# vewa-filters.net
KiCad netlist of a schematic drawn in EAGLE
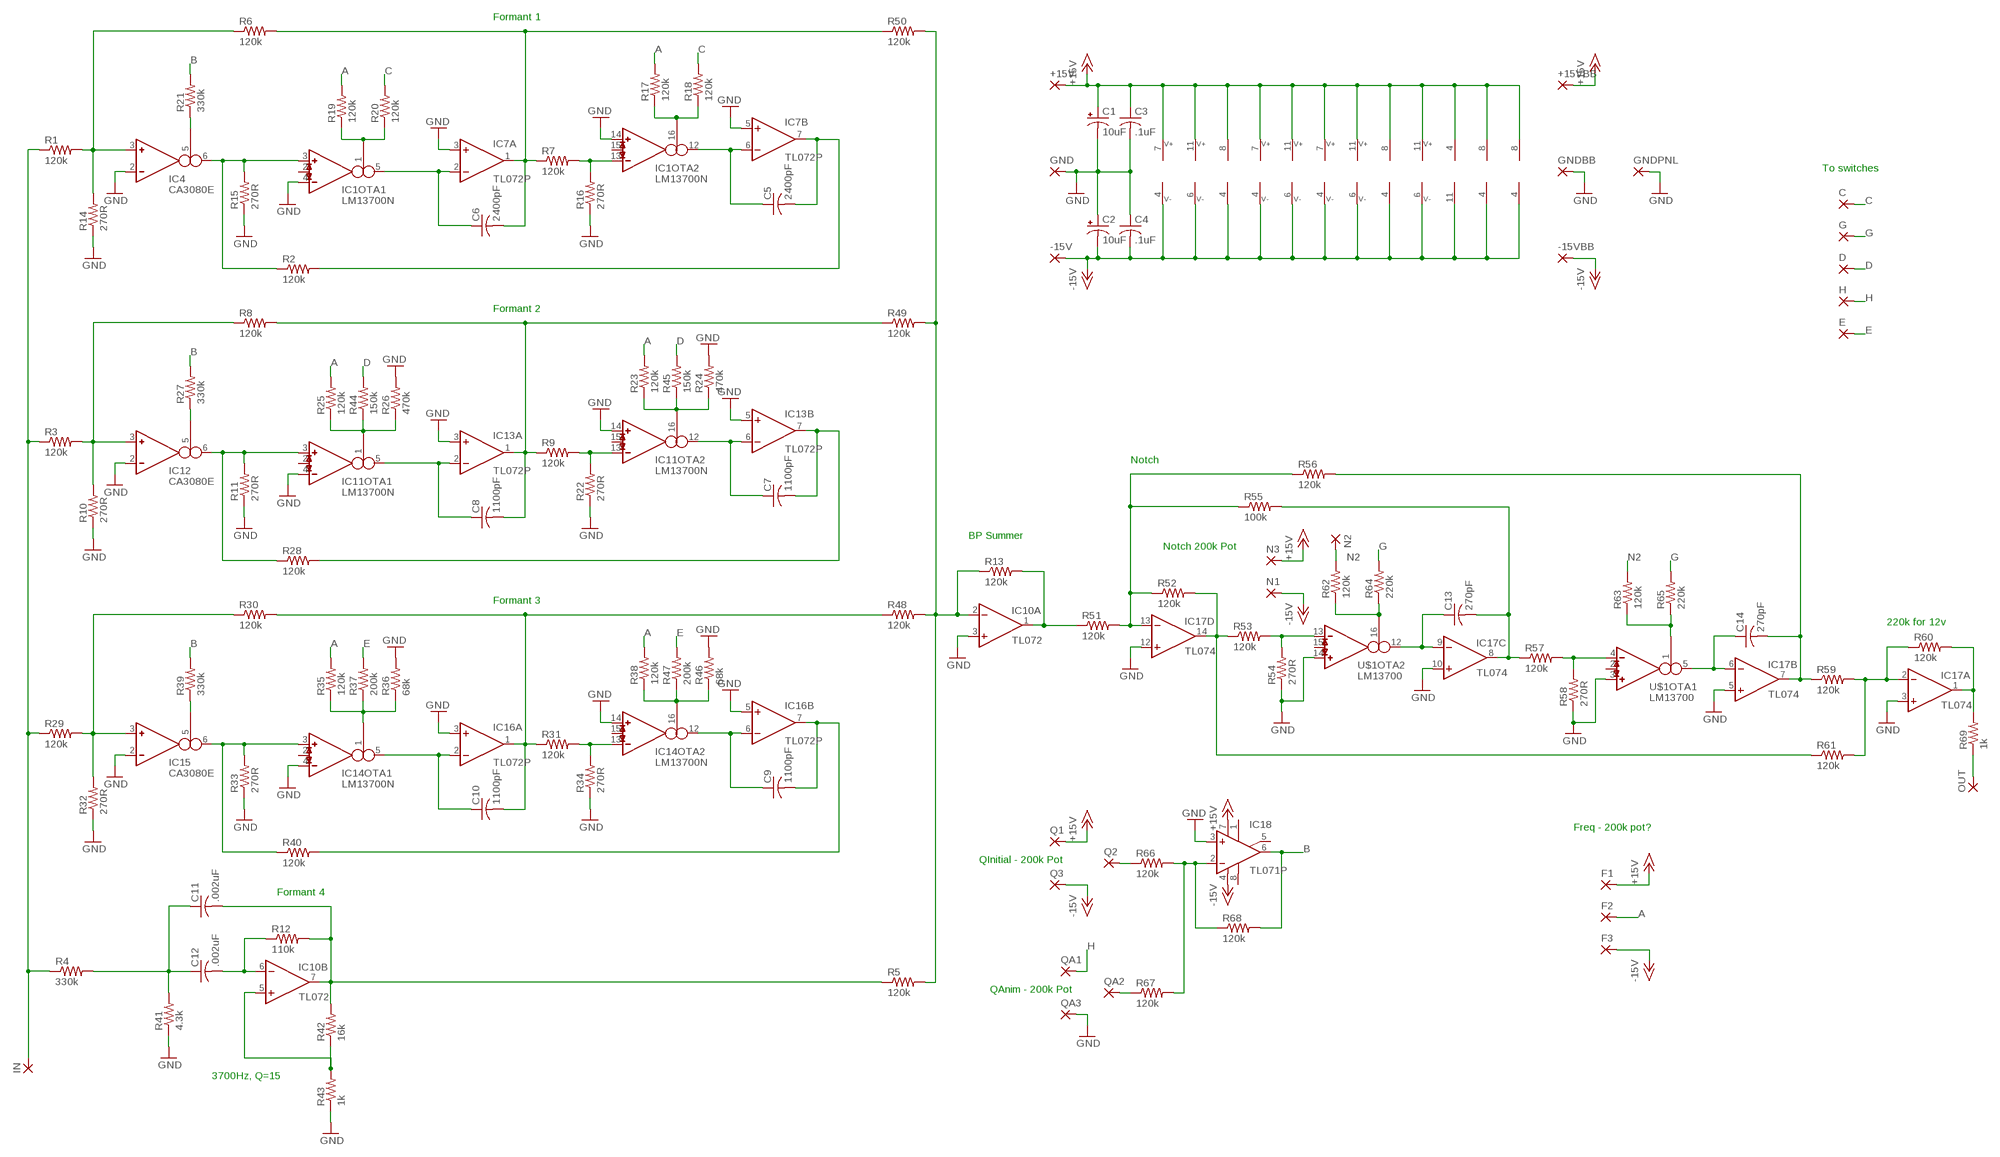
[diagram p0: schematic, sheet 1]

(export (version "E")
  (design (tool "Eeschema 10.0.6"))
  (components
    (comp (ref "+15V")
      (value "2,54/1,0")
      (footprint "eagle-import:2,54_1,0")
      (libsource (lib "eagle-import") (part "2,54/1,0"))
    )
    (comp (ref "+15VBB")
      (value "2,54/1,0")
      (footprint "eagle-import:2,54_1,0")
      (libsource (lib "eagle-import") (part "2,54/1,0"))
    )
    (comp (ref "-15V")
      (value "2,54/1,0")
      (footprint "eagle-import:2,54_1,0")
      (libsource (lib "eagle-import") (part "2,54/1,0"))
    )
    (comp (ref "-15VBB")
      (value "2,54/1,0")
      (footprint "eagle-import:2,54_1,0")
      (libsource (lib "eagle-import") (part "2,54/1,0"))
    )
    (comp (ref "C")
      (value "2,54/1,0")
      (footprint "eagle-import:2,54_1,0")
      (libsource (lib "eagle-import") (part "2,54/1,0"))
    )
    (comp (ref "C1")
      (value "10uF")
      (footprint "eagle-import:E2,5-5")
      (libsource (lib "eagle-import") (part "CPOL-USE2.5-5"))
    )
    (comp (ref "C2")
      (value "10uF")
      (footprint "eagle-import:E2,5-5")
      (libsource (lib "eagle-import") (part "CPOL-USE2.5-5"))
    )
    (comp (ref "C3")
      (value ".1uF")
      (footprint "eagle-import:C050-025X075")
      (libsource (lib "eagle-import") (part "C-US050-025X075"))
    )
    (comp (ref "C4")
      (value ".1uF")
      (footprint "eagle-import:C050-025X075")
      (libsource (lib "eagle-import") (part "C-US050-025X075"))
    )
    (comp (ref "C5")
      (value "2400pF")
      (footprint "eagle-import:C050-025X075")
      (libsource (lib "eagle-import") (part "C-US050-025X075"))
    )
    (comp (ref "C6")
      (value "2400pF")
      (footprint "eagle-import:C050-025X075")
      (libsource (lib "eagle-import") (part "C-US050-025X075"))
    )
    (comp (ref "C7")
      (value "1100pF")
      (footprint "eagle-import:C050-025X075")
      (libsource (lib "eagle-import") (part "C-US050-025X075"))
    )
    (comp (ref "C8")
      (value "1100pF")
      (footprint "eagle-import:C050-025X075")
      (libsource (lib "eagle-import") (part "C-US050-025X075"))
    )
    (comp (ref "C9")
      (value "1100pF")
      (footprint "eagle-import:C050-025X075")
      (libsource (lib "eagle-import") (part "C-US050-025X075"))
    )
    (comp (ref "C10")
      (value "1100pF")
      (footprint "eagle-import:C050-025X075")
      (libsource (lib "eagle-import") (part "C-US050-025X075"))
    )
    (comp (ref "C11")
      (value ".002uF")
      (footprint "eagle-import:C050-025X075")
      (libsource (lib "eagle-import") (part "C-US050-025X075"))
    )
    (comp (ref "C12")
      (value ".002uF")
      (footprint "eagle-import:C050-025X075")
      (libsource (lib "eagle-import") (part "C-US050-025X075"))
    )
    (comp (ref "C13")
      (value "270pF")
      (footprint "eagle-import:C050-025X075")
      (libsource (lib "eagle-import") (part "C-US050-025X075"))
    )
    (comp (ref "C14")
      (value "270pF")
      (footprint "eagle-import:C050-025X075")
      (libsource (lib "eagle-import") (part "C-US050-025X075"))
    )
    (comp (ref "D")
      (value "2,54/1,0")
      (footprint "eagle-import:2,54_1,0")
      (libsource (lib "eagle-import") (part "2,54/1,0"))
    )
    (comp (ref "E")
      (value "2,54/1,0")
      (footprint "eagle-import:2,54_1,0")
      (libsource (lib "eagle-import") (part "2,54/1,0"))
    )
    (comp (ref "F1")
      (value "2,54/1,0")
      (footprint "eagle-import:2,54_1,0")
      (libsource (lib "eagle-import") (part "2,54/1,0"))
    )
    (comp (ref "F2")
      (value "2,54/1,0")
      (footprint "eagle-import:2,54_1,0")
      (libsource (lib "eagle-import") (part "2,54/1,0"))
    )
    (comp (ref "F3")
      (value "2,54/1,0")
      (footprint "eagle-import:2,54_1,0")
      (libsource (lib "eagle-import") (part "2,54/1,0"))
    )
    (comp (ref "G")
      (value "2,54/1,0")
      (footprint "eagle-import:2,54_1,0")
      (libsource (lib "eagle-import") (part "2,54/1,0"))
    )
    (comp (ref "GND")
      (value "2,54/1,0")
      (footprint "eagle-import:2,54_1,0")
      (libsource (lib "eagle-import") (part "2,54/1,0"))
    )
    (comp (ref "GNDBB")
      (value "2,54/1,0")
      (footprint "eagle-import:2,54_1,0")
      (libsource (lib "eagle-import") (part "2,54/1,0"))
    )
    (comp (ref "GNDPNL")
      (value "2,54/1,0")
      (footprint "eagle-import:2,54_1,0")
      (libsource (lib "eagle-import") (part "2,54/1,0"))
    )
    (comp (ref "H")
      (value "2,54/1,0")
      (footprint "eagle-import:2,54_1,0")
      (libsource (lib "eagle-import") (part "2,54/1,0"))
    )
    (comp (ref "IC1")
      (value "LM13700N")
      (footprint "eagle-import:DIL16")
      (libsource (lib "eagle-import") (part "LM13700N"))
    )
    (comp (ref "IC4")
      (value "CA3080E")
      (footprint "eagle-import:DIL08")
      (libsource (lib "eagle-import") (part "CA3080E"))
    )
    (comp (ref "IC7")
      (value "TL072P")
      (footprint "eagle-import:DIL08")
      (libsource (lib "eagle-import") (part "TL072P"))
    )
    (comp (ref "IC10")
      (value "TL072")
      (footprint "eagle-import:DIL08")
      (libsource (lib "eagle-import") (part "TL072-TOPP"))
    )
    (comp (ref "IC11")
      (value "LM13700N")
      (footprint "eagle-import:DIL16")
      (libsource (lib "eagle-import") (part "LM13700N"))
    )
    (comp (ref "IC12")
      (value "CA3080E")
      (footprint "eagle-import:DIL08")
      (libsource (lib "eagle-import") (part "CA3080E"))
    )
    (comp (ref "IC13")
      (value "TL072P")
      (footprint "eagle-import:DIL08")
      (libsource (lib "eagle-import") (part "TL072P"))
    )
    (comp (ref "IC14")
      (value "LM13700N")
      (footprint "eagle-import:DIL16")
      (libsource (lib "eagle-import") (part "LM13700N"))
    )
    (comp (ref "IC15")
      (value "CA3080E")
      (footprint "eagle-import:DIL08")
      (libsource (lib "eagle-import") (part "CA3080E"))
    )
    (comp (ref "IC16")
      (value "TL072P")
      (footprint "eagle-import:DIL08")
      (libsource (lib "eagle-import") (part "TL072P"))
    )
    (comp (ref "IC17")
      (value "TL074")
      (footprint "eagle-import:DIL14")
      (libsource (lib "eagle-import") (part "TL074-TOPP"))
    )
    (comp (ref "IC18")
      (value "TL071P")
      (footprint "eagle-import:DIL08")
      (libsource (lib "eagle-import") (part "TL071P"))
    )
    (comp (ref "IN")
      (value "2,54/1,0")
      (footprint "eagle-import:2,54_1,0")
      (libsource (lib "eagle-import") (part "2,54/1,0"))
    )
    (comp (ref "N1")
      (value "2,54/1,0")
      (footprint "eagle-import:2,54_1,0")
      (libsource (lib "eagle-import") (part "2,54/1,0"))
    )
    (comp (ref "N2")
      (value "2,54/1,0")
      (footprint "eagle-import:2,54_1,0")
      (libsource (lib "eagle-import") (part "2,54/1,0"))
    )
    (comp (ref "N3")
      (value "2,54/1,0")
      (footprint "eagle-import:2,54_1,0")
      (libsource (lib "eagle-import") (part "2,54/1,0"))
    )
    (comp (ref "OUT")
      (value "2,54/1,0")
      (footprint "eagle-import:2,54_1,0")
      (libsource (lib "eagle-import") (part "2,54/1,0"))
    )
    (comp (ref "Q1")
      (value "2,54/1,0")
      (footprint "eagle-import:2,54_1,0")
      (libsource (lib "eagle-import") (part "2,54/1,0"))
    )
    (comp (ref "Q2")
      (value "2,54/1,0")
      (footprint "eagle-import:2,54_1,0")
      (libsource (lib "eagle-import") (part "2,54/1,0"))
    )
    (comp (ref "Q3")
      (value "2,54/1,0")
      (footprint "eagle-import:2,54_1,0")
      (libsource (lib "eagle-import") (part "2,54/1,0"))
    )
    (comp (ref "QA1")
      (value "2,54/1,0")
      (footprint "eagle-import:2,54_1,0")
      (libsource (lib "eagle-import") (part "2,54/1,0"))
    )
    (comp (ref "QA2")
      (value "2,54/1,0")
      (footprint "eagle-import:2,54_1,0")
      (libsource (lib "eagle-import") (part "2,54/1,0"))
    )
    (comp (ref "QA3")
      (value "2,54/1,0")
      (footprint "eagle-import:2,54_1,0")
      (libsource (lib "eagle-import") (part "2,54/1,0"))
    )
    (comp (ref "R1")
      (value "120k")
      (footprint "eagle-import:0207_10")
      (libsource (lib "eagle-import") (part "R-US_0207/10"))
    )
    (comp (ref "R2")
      (value "120k")
      (footprint "eagle-import:0207_10")
      (libsource (lib "eagle-import") (part "R-US_0207/10"))
    )
    (comp (ref "R3")
      (value "120k")
      (footprint "eagle-import:0207_10")
      (libsource (lib "eagle-import") (part "R-US_0207/10"))
    )
    (comp (ref "R4")
      (value "330k")
      (footprint "eagle-import:0207_10")
      (libsource (lib "eagle-import") (part "R-US_0207/10"))
    )
    (comp (ref "R5")
      (value "120k")
      (footprint "eagle-import:0207_10")
      (libsource (lib "eagle-import") (part "R-US_0207/10"))
    )
    (comp (ref "R6")
      (value "120k")
      (footprint "eagle-import:0207_10")
      (libsource (lib "eagle-import") (part "R-US_0207/10"))
    )
    (comp (ref "R7")
      (value "120k")
      (footprint "eagle-import:0207_10")
      (libsource (lib "eagle-import") (part "R-US_0207/10"))
    )
    (comp (ref "R8")
      (value "120k")
      (footprint "eagle-import:0207_10")
      (libsource (lib "eagle-import") (part "R-US_0207/10"))
    )
    (comp (ref "R9")
      (value "120k")
      (footprint "eagle-import:0207_10")
      (libsource (lib "eagle-import") (part "R-US_0207/10"))
    )
    (comp (ref "R10")
      (value "270R")
      (footprint "eagle-import:0207_10")
      (libsource (lib "eagle-import") (part "R-US_0207/10"))
    )
    (comp (ref "R11")
      (value "270R")
      (footprint "eagle-import:0207_10")
      (libsource (lib "eagle-import") (part "R-US_0207/10"))
    )
    (comp (ref "R12")
      (value "110k")
      (footprint "eagle-import:0207_10")
      (libsource (lib "eagle-import") (part "R-US_0207/10"))
    )
    (comp (ref "R13")
      (value "120k")
      (footprint "eagle-import:0207_10")
      (libsource (lib "eagle-import") (part "R-US_0207/10"))
    )
    (comp (ref "R14")
      (value "270R")
      (footprint "eagle-import:0207_10")
      (libsource (lib "eagle-import") (part "R-US_0207/10"))
    )
    (comp (ref "R15")
      (value "270R")
      (footprint "eagle-import:0207_10")
      (libsource (lib "eagle-import") (part "R-US_0207/10"))
    )
    (comp (ref "R16")
      (value "270R")
      (footprint "eagle-import:0207_10")
      (libsource (lib "eagle-import") (part "R-US_0207/10"))
    )
    (comp (ref "R17")
      (value "120k")
      (footprint "eagle-import:0207_10")
      (libsource (lib "eagle-import") (part "R-US_0207/10"))
    )
    (comp (ref "R18")
      (value "120k")
      (footprint "eagle-import:0207_10")
      (libsource (lib "eagle-import") (part "R-US_0207/10"))
    )
    (comp (ref "R19")
      (value "120k")
      (footprint "eagle-import:0207_10")
      (libsource (lib "eagle-import") (part "R-US_0207/10"))
    )
    (comp (ref "R20")
      (value "120k")
      (footprint "eagle-import:0207_10")
      (libsource (lib "eagle-import") (part "R-US_0207/10"))
    )
    (comp (ref "R21")
      (value "330k")
      (footprint "eagle-import:0207_10")
      (libsource (lib "eagle-import") (part "R-US_0207/10"))
    )
    (comp (ref "R22")
      (value "270R")
      (footprint "eagle-import:0207_10")
      (libsource (lib "eagle-import") (part "R-US_0207/10"))
    )
    (comp (ref "R23")
      (value "120k")
      (footprint "eagle-import:0207_10")
      (libsource (lib "eagle-import") (part "R-US_0207/10"))
    )
    (comp (ref "R24")
      (value "470k")
      (footprint "eagle-import:0207_10")
      (libsource (lib "eagle-import") (part "R-US_0207/10"))
    )
    (comp (ref "R25")
      (value "120k")
      (footprint "eagle-import:0207_10")
      (libsource (lib "eagle-import") (part "R-US_0207/10"))
    )
    (comp (ref "R26")
      (value "470k")
      (footprint "eagle-import:0207_10")
      (libsource (lib "eagle-import") (part "R-US_0207/10"))
    )
    (comp (ref "R27")
      (value "330k")
      (footprint "eagle-import:0207_10")
      (libsource (lib "eagle-import") (part "R-US_0207/10"))
    )
    (comp (ref "R28")
      (value "120k")
      (footprint "eagle-import:0207_10")
      (libsource (lib "eagle-import") (part "R-US_0207/10"))
    )
    (comp (ref "R29")
      (value "120k")
      (footprint "eagle-import:0207_10")
      (libsource (lib "eagle-import") (part "R-US_0207/10"))
    )
    (comp (ref "R30")
      (value "120k")
      (footprint "eagle-import:0207_10")
      (libsource (lib "eagle-import") (part "R-US_0207/10"))
    )
    (comp (ref "R31")
      (value "120k")
      (footprint "eagle-import:0207_10")
      (libsource (lib "eagle-import") (part "R-US_0207/10"))
    )
    (comp (ref "R32")
      (value "270R")
      (footprint "eagle-import:0207_10")
      (libsource (lib "eagle-import") (part "R-US_0207/10"))
    )
    (comp (ref "R33")
      (value "270R")
      (footprint "eagle-import:0207_10")
      (libsource (lib "eagle-import") (part "R-US_0207/10"))
    )
    (comp (ref "R34")
      (value "270R")
      (footprint "eagle-import:0207_10")
      (libsource (lib "eagle-import") (part "R-US_0207/10"))
    )
    (comp (ref "R35")
      (value "120k")
      (footprint "eagle-import:0207_10")
      (libsource (lib "eagle-import") (part "R-US_0207/10"))
    )
    (comp (ref "R36")
      (value "68k")
      (footprint "eagle-import:0207_10")
      (libsource (lib "eagle-import") (part "R-US_0207/10"))
    )
    (comp (ref "R37")
      (value "200k")
      (footprint "eagle-import:0207_10")
      (libsource (lib "eagle-import") (part "R-US_0207/10"))
    )
    (comp (ref "R38")
      (value "120k")
      (footprint "eagle-import:0207_10")
      (libsource (lib "eagle-import") (part "R-US_0207/10"))
    )
    (comp (ref "R39")
      (value "330k")
      (footprint "eagle-import:0207_10")
      (libsource (lib "eagle-import") (part "R-US_0207/10"))
    )
    (comp (ref "R40")
      (value "120k")
      (footprint "eagle-import:0207_10")
      (libsource (lib "eagle-import") (part "R-US_0207/10"))
    )
    (comp (ref "R41")
      (value "4.3k")
      (footprint "eagle-import:0207_10")
      (libsource (lib "eagle-import") (part "R-US_0207/10"))
    )
    (comp (ref "R42")
      (value "16k")
      (footprint "eagle-import:0207_10")
      (libsource (lib "eagle-import") (part "R-US_0207/10"))
    )
    (comp (ref "R43")
      (value "1k")
      (footprint "eagle-import:0207_10")
      (libsource (lib "eagle-import") (part "R-US_0207/10"))
    )
    (comp (ref "R44")
      (value "150k")
      (footprint "eagle-import:0207_10")
      (libsource (lib "eagle-import") (part "R-US_0207/10"))
    )
    (comp (ref "R45")
      (value "150k")
      (footprint "eagle-import:0207_10")
      (libsource (lib "eagle-import") (part "R-US_0207/10"))
    )
    (comp (ref "R46")
      (value "68k")
      (footprint "eagle-import:0207_10")
      (libsource (lib "eagle-import") (part "R-US_0207/10"))
    )
    (comp (ref "R47")
      (value "200k")
      (footprint "eagle-import:0207_10")
      (libsource (lib "eagle-import") (part "R-US_0207/10"))
    )
    (comp (ref "R48")
      (value "120k")
      (footprint "eagle-import:0207_10")
      (libsource (lib "eagle-import") (part "R-US_0207/10"))
    )
    (comp (ref "R49")
      (value "120k")
      (footprint "eagle-import:0207_10")
      (libsource (lib "eagle-import") (part "R-US_0207/10"))
    )
    (comp (ref "R50")
      (value "120k")
      (footprint "eagle-import:0207_10")
      (libsource (lib "eagle-import") (part "R-US_0207/10"))
    )
    (comp (ref "R51")
      (value "120k")
      (footprint "eagle-import:0207_10")
      (libsource (lib "eagle-import") (part "R-US_0207/10"))
    )
    (comp (ref "R52")
      (value "120k")
      (footprint "eagle-import:0207_10")
      (libsource (lib "eagle-import") (part "R-US_0207/10"))
    )
    (comp (ref "R53")
      (value "120k")
      (footprint "eagle-import:0207_10")
      (libsource (lib "eagle-import") (part "R-US_0207/10"))
    )
    (comp (ref "R54")
      (value "270R")
      (footprint "eagle-import:0207_10")
      (libsource (lib "eagle-import") (part "R-US_0207/10"))
    )
    (comp (ref "R55")
      (value "100k")
      (footprint "eagle-import:0207_10")
      (libsource (lib "eagle-import") (part "R-US_0207/10"))
    )
    (comp (ref "R56")
      (value "120k")
      (footprint "eagle-import:0207_10")
      (libsource (lib "eagle-import") (part "R-US_0207/10"))
    )
    (comp (ref "R57")
      (value "120k")
      (footprint "eagle-import:0207_10")
      (libsource (lib "eagle-import") (part "R-US_0207/10"))
    )
    (comp (ref "R58")
      (value "270R")
      (footprint "eagle-import:0207_10")
      (libsource (lib "eagle-import") (part "R-US_0207/10"))
    )
    (comp (ref "R59")
      (value "120k")
      (footprint "eagle-import:0207_10")
      (libsource (lib "eagle-import") (part "R-US_0207/10"))
    )
    (comp (ref "R60")
      (value "120k")
      (footprint "eagle-import:0207_10")
      (libsource (lib "eagle-import") (part "R-US_0207/10"))
    )
    (comp (ref "R61")
      (value "120k")
      (footprint "eagle-import:0207_10")
      (libsource (lib "eagle-import") (part "R-US_0207/10"))
    )
    (comp (ref "R62")
      (value "120k")
      (footprint "eagle-import:0207_10")
      (libsource (lib "eagle-import") (part "R-US_0207/10"))
    )
    (comp (ref "R63")
      (value "120k")
      (footprint "eagle-import:0207_10")
      (libsource (lib "eagle-import") (part "R-US_0207/10"))
    )
    (comp (ref "R64")
      (value "220k")
      (footprint "eagle-import:0207_10")
      (libsource (lib "eagle-import") (part "R-US_0207/10"))
    )
    (comp (ref "R65")
      (value "220k")
      (footprint "eagle-import:0207_10")
      (libsource (lib "eagle-import") (part "R-US_0207/10"))
    )
    (comp (ref "R66")
      (value "120k")
      (footprint "eagle-import:0207_10")
      (libsource (lib "eagle-import") (part "R-US_0207/10"))
    )
    (comp (ref "R67")
      (value "120k")
      (footprint "eagle-import:0207_10")
      (libsource (lib "eagle-import") (part "R-US_0207/10"))
    )
    (comp (ref "R68")
      (value "120k")
      (footprint "eagle-import:0207_10")
      (libsource (lib "eagle-import") (part "R-US_0207/10"))
    )
    (comp (ref "R69")
      (value "1k")
      (footprint "eagle-import:0207_10")
      (libsource (lib "eagle-import") (part "R-US_0207/10"))
    )
    (comp (ref "U$1")
      (value "LM13700")
      (footprint "eagle-import:DIL16")
      (libsource (lib "eagle-import") (part "LM13700-TOPDIP16"))
    )
  )
  (nets
    (net (code "1") (name "+15V") (class "Default")
      (node (ref "+15V") (pin "1") (pinfunction "P_1") (pintype "passive"))
      (node (ref "+15VBB") (pin "1") (pinfunction "P_1") (pintype "passive"))
      (node (ref "C1") (pin "+") (pinfunction "+_+") (pintype "passive"))
      (node (ref "C3") (pin "1") (pinfunction "1_1") (pintype "passive"))
      (node (ref "F1") (pin "1") (pinfunction "P_1") (pintype "passive"))
      (node (ref "IC1") (pin "11") (pinfunction "7_11") (pintype "passive"))
      (node (ref "IC10") (pin "8") (pinfunction "V+_8") (pintype "power_in"))
      (node (ref "IC11") (pin "11") (pinfunction "7_11") (pintype "passive"))
      (node (ref "IC12") (pin "7") (pinfunction "7_7") (pintype "passive"))
      (node (ref "IC13") (pin "8") (pinfunction "V+_8") (pintype "power_in"))
      (node (ref "IC14") (pin "11") (pinfunction "7_11") (pintype "passive"))
      (node (ref "IC15") (pin "7") (pinfunction "7_7") (pintype "passive"))
      (node (ref "IC16") (pin "8") (pinfunction "V+_8") (pintype "power_in"))
      (node (ref "IC17") (pin "4") (pinfunction "V+_4") (pintype "power_in"))
      (node (ref "IC18") (pin "7") (pinfunction "V+_7") (pintype "power_in"))
      (node (ref "IC4") (pin "7") (pinfunction "7_7") (pintype "passive"))
      (node (ref "IC7") (pin "8") (pinfunction "V+_8") (pintype "power_in"))
      (node (ref "N3") (pin "1") (pinfunction "P_1") (pintype "passive"))
      (node (ref "Q1") (pin "1") (pinfunction "P_1") (pintype "passive"))
      (node (ref "U$1") (pin "11") (pinfunction "7_11") (pintype "passive"))
    )
    (net (code "2") (name "-15V") (class "Default")
      (node (ref "-15V") (pin "1") (pinfunction "P_1") (pintype "passive"))
      (node (ref "-15VBB") (pin "1") (pinfunction "P_1") (pintype "passive"))
      (node (ref "C2") (pin "-") (pinfunction "-_-") (pintype "passive"))
      (node (ref "C4") (pin "2") (pinfunction "2_2") (pintype "passive"))
      (node (ref "F3") (pin "1") (pinfunction "P_1") (pintype "passive"))
      (node (ref "IC1") (pin "6") (pinfunction "4_6") (pintype "passive"))
      (node (ref "IC10") (pin "4") (pinfunction "V-_4") (pintype "power_in"))
      (node (ref "IC11") (pin "6") (pinfunction "4_6") (pintype "passive"))
      (node (ref "IC12") (pin "4") (pinfunction "4_4") (pintype "passive"))
      (node (ref "IC13") (pin "4") (pinfunction "V-_4") (pintype "power_in"))
      (node (ref "IC14") (pin "6") (pinfunction "4_6") (pintype "passive"))
      (node (ref "IC15") (pin "4") (pinfunction "4_4") (pintype "passive"))
      (node (ref "IC16") (pin "4") (pinfunction "V-_4") (pintype "power_in"))
      (node (ref "IC17") (pin "11") (pinfunction "V-_11") (pintype "power_in"))
      (node (ref "IC18") (pin "4") (pinfunction "V-_4") (pintype "power_in"))
      (node (ref "IC4") (pin "4") (pinfunction "4_4") (pintype "passive"))
      (node (ref "IC7") (pin "4") (pinfunction "V-_4") (pintype "power_in"))
      (node (ref "N1") (pin "1") (pinfunction "P_1") (pintype "passive"))
      (node (ref "Q3") (pin "1") (pinfunction "P_1") (pintype "passive"))
      (node (ref "U$1") (pin "6") (pinfunction "4_6") (pintype "passive"))
    )
    (net (code "3") (name "/A") (class "Default")
      (node (ref "F2") (pin "1") (pinfunction "P_1") (pintype "passive"))
      (node (ref "R17") (pin "2") (pinfunction "2_2") (pintype "passive"))
      (node (ref "R19") (pin "2") (pinfunction "2_2") (pintype "passive"))
      (node (ref "R23") (pin "2") (pinfunction "2_2") (pintype "passive"))
      (node (ref "R25") (pin "2") (pinfunction "2_2") (pintype "passive"))
      (node (ref "R35") (pin "2") (pinfunction "2_2") (pintype "passive"))
      (node (ref "R38") (pin "2") (pinfunction "2_2") (pintype "passive"))
    )
    (net (code "4") (name "/B") (class "Default")
      (node (ref "IC18") (pin "6") (pinfunction "OUT_6") (pintype "output"))
      (node (ref "R21") (pin "2") (pinfunction "2_2") (pintype "passive"))
      (node (ref "R27") (pin "2") (pinfunction "2_2") (pintype "passive"))
      (node (ref "R39") (pin "2") (pinfunction "2_2") (pintype "passive"))
      (node (ref "R68") (pin "2") (pinfunction "2_2") (pintype "passive"))
    )
    (net (code "5") (name "/C") (class "Default")
      (node (ref "C") (pin "1") (pinfunction "P_1") (pintype "passive"))
      (node (ref "R18") (pin "2") (pinfunction "2_2") (pintype "passive"))
      (node (ref "R20") (pin "2") (pinfunction "2_2") (pintype "passive"))
    )
    (net (code "6") (name "/D") (class "Default")
      (node (ref "D") (pin "1") (pinfunction "P_1") (pintype "passive"))
      (node (ref "R44") (pin "2") (pinfunction "2_2") (pintype "passive"))
      (node (ref "R45") (pin "2") (pinfunction "2_2") (pintype "passive"))
    )
    (net (code "7") (name "/E") (class "Default")
      (node (ref "E") (pin "1") (pinfunction "P_1") (pintype "passive"))
      (node (ref "R37") (pin "2") (pinfunction "2_2") (pintype "passive"))
      (node (ref "R47") (pin "2") (pinfunction "2_2") (pintype "passive"))
    )
    (net (code "8") (name "/G") (class "Default")
      (node (ref "G") (pin "1") (pinfunction "P_1") (pintype "passive"))
      (node (ref "R64") (pin "2") (pinfunction "2_2") (pintype "passive"))
      (node (ref "R65") (pin "2") (pinfunction "2_2") (pintype "passive"))
    )
    (net (code "9") (name "/H") (class "Default")
      (node (ref "H") (pin "1") (pinfunction "P_1") (pintype "passive"))
      (node (ref "QA1") (pin "1") (pinfunction "P_1") (pintype "passive"))
    )
    (net (code "10") (name "/N2") (class "Default")
      (node (ref "N2") (pin "1") (pinfunction "P_1") (pintype "passive"))
      (node (ref "R62") (pin "2") (pinfunction "2_2") (pintype "passive"))
      (node (ref "R63") (pin "2") (pinfunction "2_2") (pintype "passive"))
    )
    (net (code "11") (name "GND") (class "Default")
      (node (ref "C1") (pin "-") (pinfunction "-_-") (pintype "passive"))
      (node (ref "C2") (pin "+") (pinfunction "+_+") (pintype "passive"))
      (node (ref "C3") (pin "2") (pinfunction "2_2") (pintype "passive"))
      (node (ref "C4") (pin "1") (pinfunction "1_1") (pintype "passive"))
      (node (ref "GND") (pin "1") (pinfunction "P_1") (pintype "passive"))
      (node (ref "GNDBB") (pin "1") (pinfunction "P_1") (pintype "passive"))
      (node (ref "GNDPNL") (pin "1") (pinfunction "P_1") (pintype "passive"))
      (node (ref "IC1") (pin "14") (pinfunction "IN_P_14") (pintype "input"))
      (node (ref "IC1") (pin "4") (pinfunction "IN_N_4") (pintype "input"))
      (node (ref "IC10") (pin "3") (pinfunction "+IN_3") (pintype "input"))
      (node (ref "IC11") (pin "14") (pinfunction "IN_P_14") (pintype "input"))
      (node (ref "IC11") (pin "4") (pinfunction "IN_N_4") (pintype "input"))
      (node (ref "IC12") (pin "2") (pinfunction "IN_N_2") (pintype "input"))
      (node (ref "IC13") (pin "3") (pinfunction "+IN_3") (pintype "input"))
      (node (ref "IC13") (pin "5") (pinfunction "+IN_5") (pintype "input"))
      (node (ref "IC14") (pin "14") (pinfunction "IN_P_14") (pintype "input"))
      (node (ref "IC14") (pin "4") (pinfunction "IN_N_4") (pintype "input"))
      (node (ref "IC15") (pin "2") (pinfunction "IN_N_2") (pintype "input"))
      (node (ref "IC16") (pin "3") (pinfunction "+IN_3") (pintype "input"))
      (node (ref "IC16") (pin "5") (pinfunction "+IN_5") (pintype "input"))
      (node (ref "IC17") (pin "10") (pinfunction "+IN_10") (pintype "input"))
      (node (ref "IC17") (pin "12") (pinfunction "+IN_12") (pintype "input"))
      (node (ref "IC17") (pin "3") (pinfunction "+IN_3") (pintype "input"))
      (node (ref "IC17") (pin "5") (pinfunction "+IN_5") (pintype "input"))
      (node (ref "IC18") (pin "3") (pinfunction "+IN_3") (pintype "input"))
      (node (ref "IC4") (pin "2") (pinfunction "IN_N_2") (pintype "input"))
      (node (ref "IC7") (pin "3") (pinfunction "+IN_3") (pintype "input"))
      (node (ref "IC7") (pin "5") (pinfunction "+IN_5") (pintype "input"))
      (node (ref "QA3") (pin "1") (pinfunction "P_1") (pintype "passive"))
      (node (ref "R10") (pin "1") (pinfunction "1_1") (pintype "passive"))
      (node (ref "R11") (pin "1") (pinfunction "1_1") (pintype "passive"))
      (node (ref "R14") (pin "1") (pinfunction "1_1") (pintype "passive"))
      (node (ref "R15") (pin "1") (pinfunction "1_1") (pintype "passive"))
      (node (ref "R16") (pin "1") (pinfunction "1_1") (pintype "passive"))
      (node (ref "R22") (pin "1") (pinfunction "1_1") (pintype "passive"))
      (node (ref "R24") (pin "2") (pinfunction "2_2") (pintype "passive"))
      (node (ref "R26") (pin "2") (pinfunction "2_2") (pintype "passive"))
      (node (ref "R32") (pin "1") (pinfunction "1_1") (pintype "passive"))
      (node (ref "R33") (pin "1") (pinfunction "1_1") (pintype "passive"))
      (node (ref "R34") (pin "1") (pinfunction "1_1") (pintype "passive"))
      (node (ref "R36") (pin "2") (pinfunction "2_2") (pintype "passive"))
      (node (ref "R41") (pin "1") (pinfunction "1_1") (pintype "passive"))
      (node (ref "R43") (pin "1") (pinfunction "1_1") (pintype "passive"))
      (node (ref "R46") (pin "2") (pinfunction "2_2") (pintype "passive"))
      (node (ref "R54") (pin "1") (pinfunction "1_1") (pintype "passive"))
      (node (ref "R58") (pin "1") (pinfunction "1_1") (pintype "passive"))
      (node (ref "U$1") (pin "14") (pinfunction "IN_P_14") (pintype "input"))
      (node (ref "U$1") (pin "3") (pinfunction "IN_P_3") (pintype "input"))
    )
    (net (code "12") (name "Net-(C11-Pad1)") (class "Default")
      (node (ref "C11") (pin "1") (pinfunction "1_1") (pintype "passive"))
      (node (ref "C12") (pin "1") (pinfunction "1_1") (pintype "passive"))
      (node (ref "R4") (pin "2") (pinfunction "2_2") (pintype "passive"))
      (node (ref "R41") (pin "2") (pinfunction "2_2") (pintype "passive"))
    )
    (net (code "13") (name "Net-(IC1C-IN_P)") (class "Default")
      (node (ref "IC1") (pin "3") (pinfunction "IN_P_3") (pintype "input"))
      (node (ref "IC4") (pin "6") (pinfunction "OUT_6") (pintype "output"))
      (node (ref "R15") (pin "2") (pinfunction "2_2") (pintype "passive"))
      (node (ref "R2") (pin "1") (pinfunction "1_1") (pintype "passive"))
    )
    (net (code "14") (name "Net-(IC1C-I_BIAS)") (class "Default")
      (node (ref "IC1") (pin "1") (pinfunction "I_BIAS_1") (pintype "input"))
      (node (ref "R19") (pin "1") (pinfunction "1_1") (pintype "passive"))
      (node (ref "R20") (pin "1") (pinfunction "1_1") (pintype "passive"))
    )
    (net (code "15") (name "Net-(IC1C-OUT)") (class "Default")
      (node (ref "C6") (pin "1") (pinfunction "1_1") (pintype "passive"))
      (node (ref "IC1") (pin "5") (pinfunction "OUT_5") (pintype "output"))
      (node (ref "IC7") (pin "2") (pinfunction "-IN_2") (pintype "input"))
    )
    (net (code "16") (name "Net-(IC1D-IN_N)") (class "Default")
      (node (ref "IC1") (pin "13") (pinfunction "IN_N_13") (pintype "input"))
      (node (ref "R16") (pin "2") (pinfunction "2_2") (pintype "passive"))
      (node (ref "R7") (pin "2") (pinfunction "2_2") (pintype "passive"))
    )
    (net (code "17") (name "Net-(IC1D-I_BIAS)") (class "Default")
      (node (ref "IC1") (pin "16") (pinfunction "I_BIAS_16") (pintype "input"))
      (node (ref "R17") (pin "1") (pinfunction "1_1") (pintype "passive"))
      (node (ref "R18") (pin "1") (pinfunction "1_1") (pintype "passive"))
    )
    (net (code "18") (name "Net-(IC1D-OUT)") (class "Default")
      (node (ref "C5") (pin "1") (pinfunction "1_1") (pintype "passive"))
      (node (ref "IC1") (pin "12") (pinfunction "OUT_12") (pintype "output"))
      (node (ref "IC7") (pin "6") (pinfunction "-IN_6") (pintype "input"))
    )
    (net (code "19") (name "Net-(IC4A-IN_P)") (class "Default")
      (node (ref "IC4") (pin "3") (pinfunction "IN_P_3") (pintype "input"))
      (node (ref "R1") (pin "2") (pinfunction "2_2") (pintype "passive"))
      (node (ref "R14") (pin "2") (pinfunction "2_2") (pintype "passive"))
      (node (ref "R6") (pin "1") (pinfunction "1_1") (pintype "passive"))
    )
    (net (code "20") (name "Net-(IC4A-I_BIAS)") (class "Default")
      (node (ref "IC4") (pin "5") (pinfunction "I_BIAS_5") (pintype "input"))
      (node (ref "R21") (pin "1") (pinfunction "1_1") (pintype "passive"))
    )
    (net (code "21") (name "Net-(IC7A-OUT)") (class "Default")
      (node (ref "C6") (pin "2") (pinfunction "2_2") (pintype "passive"))
      (node (ref "IC7") (pin "1") (pinfunction "OUT_1") (pintype "output"))
      (node (ref "R50") (pin "1") (pinfunction "1_1") (pintype "passive"))
      (node (ref "R6") (pin "2") (pinfunction "2_2") (pintype "passive"))
      (node (ref "R7") (pin "1") (pinfunction "1_1") (pintype "passive"))
    )
    (net (code "22") (name "Net-(IC7B-OUT)") (class "Default")
      (node (ref "C5") (pin "2") (pinfunction "2_2") (pintype "passive"))
      (node (ref "IC7") (pin "7") (pinfunction "OUT_7") (pintype "output"))
      (node (ref "R2") (pin "2") (pinfunction "2_2") (pintype "passive"))
    )
    (net (code "23") (name "Net-(IC10A--IN)") (class "Default")
      (node (ref "IC10") (pin "2") (pinfunction "-IN_2") (pintype "input"))
      (node (ref "R13") (pin "1") (pinfunction "1_1") (pintype "passive"))
      (node (ref "R48") (pin "2") (pinfunction "2_2") (pintype "passive"))
      (node (ref "R49") (pin "2") (pinfunction "2_2") (pintype "passive"))
      (node (ref "R5") (pin "2") (pinfunction "2_2") (pintype "passive"))
      (node (ref "R50") (pin "2") (pinfunction "2_2") (pintype "passive"))
    )
    (net (code "24") (name "Net-(IC10A-OUT)") (class "Default")
      (node (ref "IC10") (pin "1") (pinfunction "OUT_1") (pintype "output"))
      (node (ref "R13") (pin "2") (pinfunction "2_2") (pintype "passive"))
      (node (ref "R51") (pin "1") (pinfunction "1_1") (pintype "passive"))
    )
    (net (code "25") (name "Net-(IC10B-+IN)") (class "Default")
      (node (ref "IC10") (pin "5") (pinfunction "+IN_5") (pintype "input"))
      (node (ref "R42") (pin "1") (pinfunction "1_1") (pintype "passive"))
      (node (ref "R43") (pin "2") (pinfunction "2_2") (pintype "passive"))
    )
    (net (code "26") (name "Net-(IC10B--IN)") (class "Default")
      (node (ref "C12") (pin "2") (pinfunction "2_2") (pintype "passive"))
      (node (ref "IC10") (pin "6") (pinfunction "-IN_6") (pintype "input"))
      (node (ref "R12") (pin "1") (pinfunction "1_1") (pintype "passive"))
    )
    (net (code "27") (name "Net-(IC10B-OUT)") (class "Default")
      (node (ref "C11") (pin "2") (pinfunction "2_2") (pintype "passive"))
      (node (ref "IC10") (pin "7") (pinfunction "OUT_7") (pintype "output"))
      (node (ref "R12") (pin "2") (pinfunction "2_2") (pintype "passive"))
      (node (ref "R42") (pin "2") (pinfunction "2_2") (pintype "passive"))
      (node (ref "R5") (pin "1") (pinfunction "1_1") (pintype "passive"))
    )
    (net (code "28") (name "Net-(IC11C-IN_P)") (class "Default")
      (node (ref "IC11") (pin "3") (pinfunction "IN_P_3") (pintype "input"))
      (node (ref "IC12") (pin "6") (pinfunction "OUT_6") (pintype "output"))
      (node (ref "R11") (pin "2") (pinfunction "2_2") (pintype "passive"))
      (node (ref "R28") (pin "1") (pinfunction "1_1") (pintype "passive"))
    )
    (net (code "29") (name "Net-(IC11C-I_BIAS)") (class "Default")
      (node (ref "IC11") (pin "1") (pinfunction "I_BIAS_1") (pintype "input"))
      (node (ref "R25") (pin "1") (pinfunction "1_1") (pintype "passive"))
      (node (ref "R26") (pin "1") (pinfunction "1_1") (pintype "passive"))
      (node (ref "R44") (pin "1") (pinfunction "1_1") (pintype "passive"))
    )
    (net (code "30") (name "Net-(IC11C-OUT)") (class "Default")
      (node (ref "C8") (pin "1") (pinfunction "1_1") (pintype "passive"))
      (node (ref "IC11") (pin "5") (pinfunction "OUT_5") (pintype "output"))
      (node (ref "IC13") (pin "2") (pinfunction "-IN_2") (pintype "input"))
    )
    (net (code "31") (name "Net-(IC11D-IN_N)") (class "Default")
      (node (ref "IC11") (pin "13") (pinfunction "IN_N_13") (pintype "input"))
      (node (ref "R22") (pin "2") (pinfunction "2_2") (pintype "passive"))
      (node (ref "R9") (pin "2") (pinfunction "2_2") (pintype "passive"))
    )
    (net (code "32") (name "Net-(IC11D-I_BIAS)") (class "Default")
      (node (ref "IC11") (pin "16") (pinfunction "I_BIAS_16") (pintype "input"))
      (node (ref "R23") (pin "1") (pinfunction "1_1") (pintype "passive"))
      (node (ref "R24") (pin "1") (pinfunction "1_1") (pintype "passive"))
      (node (ref "R45") (pin "1") (pinfunction "1_1") (pintype "passive"))
    )
    (net (code "33") (name "Net-(IC11D-OUT)") (class "Default")
      (node (ref "C7") (pin "1") (pinfunction "1_1") (pintype "passive"))
      (node (ref "IC11") (pin "12") (pinfunction "OUT_12") (pintype "output"))
      (node (ref "IC13") (pin "6") (pinfunction "-IN_6") (pintype "input"))
    )
    (net (code "34") (name "Net-(IC12A-IN_P)") (class "Default")
      (node (ref "IC12") (pin "3") (pinfunction "IN_P_3") (pintype "input"))
      (node (ref "R10") (pin "2") (pinfunction "2_2") (pintype "passive"))
      (node (ref "R3") (pin "2") (pinfunction "2_2") (pintype "passive"))
      (node (ref "R8") (pin "1") (pinfunction "1_1") (pintype "passive"))
    )
    (net (code "35") (name "Net-(IC12A-I_BIAS)") (class "Default")
      (node (ref "IC12") (pin "5") (pinfunction "I_BIAS_5") (pintype "input"))
      (node (ref "R27") (pin "1") (pinfunction "1_1") (pintype "passive"))
    )
    (net (code "36") (name "Net-(IC13A-OUT)") (class "Default")
      (node (ref "C8") (pin "2") (pinfunction "2_2") (pintype "passive"))
      (node (ref "IC13") (pin "1") (pinfunction "OUT_1") (pintype "output"))
      (node (ref "R49") (pin "1") (pinfunction "1_1") (pintype "passive"))
      (node (ref "R8") (pin "2") (pinfunction "2_2") (pintype "passive"))
      (node (ref "R9") (pin "1") (pinfunction "1_1") (pintype "passive"))
    )
    (net (code "37") (name "Net-(IC13B-OUT)") (class "Default")
      (node (ref "C7") (pin "2") (pinfunction "2_2") (pintype "passive"))
      (node (ref "IC13") (pin "7") (pinfunction "OUT_7") (pintype "output"))
      (node (ref "R28") (pin "2") (pinfunction "2_2") (pintype "passive"))
    )
    (net (code "38") (name "Net-(IC14C-IN_P)") (class "Default")
      (node (ref "IC14") (pin "3") (pinfunction "IN_P_3") (pintype "input"))
      (node (ref "IC15") (pin "6") (pinfunction "OUT_6") (pintype "output"))
      (node (ref "R33") (pin "2") (pinfunction "2_2") (pintype "passive"))
      (node (ref "R40") (pin "1") (pinfunction "1_1") (pintype "passive"))
    )
    (net (code "39") (name "Net-(IC14C-I_BIAS)") (class "Default")
      (node (ref "IC14") (pin "1") (pinfunction "I_BIAS_1") (pintype "input"))
      (node (ref "R35") (pin "1") (pinfunction "1_1") (pintype "passive"))
      (node (ref "R36") (pin "1") (pinfunction "1_1") (pintype "passive"))
      (node (ref "R37") (pin "1") (pinfunction "1_1") (pintype "passive"))
    )
    (net (code "40") (name "Net-(IC14C-OUT)") (class "Default")
      (node (ref "C10") (pin "1") (pinfunction "1_1") (pintype "passive"))
      (node (ref "IC14") (pin "5") (pinfunction "OUT_5") (pintype "output"))
      (node (ref "IC16") (pin "2") (pinfunction "-IN_2") (pintype "input"))
    )
    (net (code "41") (name "Net-(IC14D-IN_N)") (class "Default")
      (node (ref "IC14") (pin "13") (pinfunction "IN_N_13") (pintype "input"))
      (node (ref "R31") (pin "2") (pinfunction "2_2") (pintype "passive"))
      (node (ref "R34") (pin "2") (pinfunction "2_2") (pintype "passive"))
    )
    (net (code "42") (name "Net-(IC14D-I_BIAS)") (class "Default")
      (node (ref "IC14") (pin "16") (pinfunction "I_BIAS_16") (pintype "input"))
      (node (ref "R38") (pin "1") (pinfunction "1_1") (pintype "passive"))
      (node (ref "R46") (pin "1") (pinfunction "1_1") (pintype "passive"))
      (node (ref "R47") (pin "1") (pinfunction "1_1") (pintype "passive"))
    )
    (net (code "43") (name "Net-(IC14D-OUT)") (class "Default")
      (node (ref "C9") (pin "1") (pinfunction "1_1") (pintype "passive"))
      (node (ref "IC14") (pin "12") (pinfunction "OUT_12") (pintype "output"))
      (node (ref "IC16") (pin "6") (pinfunction "-IN_6") (pintype "input"))
    )
    (net (code "44") (name "Net-(IC15A-IN_P)") (class "Default")
      (node (ref "IC15") (pin "3") (pinfunction "IN_P_3") (pintype "input"))
      (node (ref "R29") (pin "2") (pinfunction "2_2") (pintype "passive"))
      (node (ref "R30") (pin "1") (pinfunction "1_1") (pintype "passive"))
      (node (ref "R32") (pin "2") (pinfunction "2_2") (pintype "passive"))
    )
    (net (code "45") (name "Net-(IC15A-I_BIAS)") (class "Default")
      (node (ref "IC15") (pin "5") (pinfunction "I_BIAS_5") (pintype "input"))
      (node (ref "R39") (pin "1") (pinfunction "1_1") (pintype "passive"))
    )
    (net (code "46") (name "Net-(IC16A-OUT)") (class "Default")
      (node (ref "C10") (pin "2") (pinfunction "2_2") (pintype "passive"))
      (node (ref "IC16") (pin "1") (pinfunction "OUT_1") (pintype "output"))
      (node (ref "R30") (pin "2") (pinfunction "2_2") (pintype "passive"))
      (node (ref "R31") (pin "1") (pinfunction "1_1") (pintype "passive"))
      (node (ref "R48") (pin "1") (pinfunction "1_1") (pintype "passive"))
    )
    (net (code "47") (name "Net-(IC16B-OUT)") (class "Default")
      (node (ref "C9") (pin "2") (pinfunction "2_2") (pintype "passive"))
      (node (ref "IC16") (pin "7") (pinfunction "OUT_7") (pintype "output"))
      (node (ref "R40") (pin "2") (pinfunction "2_2") (pintype "passive"))
    )
    (net (code "48") (name "Net-(IC17A--IN)") (class "Default")
      (node (ref "IC17") (pin "2") (pinfunction "-IN_2") (pintype "input"))
      (node (ref "R59") (pin "2") (pinfunction "2_2") (pintype "passive"))
      (node (ref "R60") (pin "1") (pinfunction "1_1") (pintype "passive"))
      (node (ref "R61") (pin "2") (pinfunction "2_2") (pintype "passive"))
    )
    (net (code "49") (name "Net-(IC17A-OUT)") (class "Default")
      (node (ref "IC17") (pin "1") (pinfunction "OUT_1") (pintype "output"))
      (node (ref "R60") (pin "2") (pinfunction "2_2") (pintype "passive"))
      (node (ref "R69") (pin "2") (pinfunction "2_2") (pintype "passive"))
    )
    (net (code "50") (name "Net-(IC17B--IN)") (class "Default")
      (node (ref "C14") (pin "1") (pinfunction "1_1") (pintype "passive"))
      (node (ref "IC17") (pin "6") (pinfunction "-IN_6") (pintype "input"))
      (node (ref "U$1") (pin "5") (pinfunction "OUT_5") (pintype "output"))
    )
    (net (code "51") (name "Net-(IC17B-OUT)") (class "Default")
      (node (ref "C14") (pin "2") (pinfunction "2_2") (pintype "passive"))
      (node (ref "IC17") (pin "7") (pinfunction "OUT_7") (pintype "output"))
      (node (ref "R56") (pin "2") (pinfunction "2_2") (pintype "passive"))
      (node (ref "R59") (pin "1") (pinfunction "1_1") (pintype "passive"))
    )
    (net (code "52") (name "Net-(IC17C--IN)") (class "Default")
      (node (ref "C13") (pin "1") (pinfunction "1_1") (pintype "passive"))
      (node (ref "IC17") (pin "9") (pinfunction "-IN_9") (pintype "input"))
      (node (ref "U$1") (pin "12") (pinfunction "OUT_12") (pintype "output"))
    )
    (net (code "53") (name "Net-(IC17C-OUT)") (class "Default")
      (node (ref "C13") (pin "2") (pinfunction "2_2") (pintype "passive"))
      (node (ref "IC17") (pin "8") (pinfunction "OUT_8") (pintype "output"))
      (node (ref "R55") (pin "2") (pinfunction "2_2") (pintype "passive"))
      (node (ref "R57") (pin "1") (pinfunction "1_1") (pintype "passive"))
    )
    (net (code "54") (name "Net-(IC17D--IN)") (class "Default")
      (node (ref "IC17") (pin "13") (pinfunction "-IN_13") (pintype "input"))
      (node (ref "R51") (pin "2") (pinfunction "2_2") (pintype "passive"))
      (node (ref "R52") (pin "1") (pinfunction "1_1") (pintype "passive"))
      (node (ref "R55") (pin "1") (pinfunction "1_1") (pintype "passive"))
      (node (ref "R56") (pin "1") (pinfunction "1_1") (pintype "passive"))
    )
    (net (code "55") (name "Net-(IC17D-OUT)") (class "Default")
      (node (ref "IC17") (pin "14") (pinfunction "OUT_14") (pintype "output"))
      (node (ref "R52") (pin "2") (pinfunction "2_2") (pintype "passive"))
      (node (ref "R53") (pin "1") (pinfunction "1_1") (pintype "passive"))
      (node (ref "R61") (pin "1") (pinfunction "1_1") (pintype "passive"))
    )
    (net (code "56") (name "Net-(IC18--IN)") (class "Default")
      (node (ref "IC18") (pin "2") (pinfunction "-IN_2") (pintype "input"))
      (node (ref "R66") (pin "2") (pinfunction "2_2") (pintype "passive"))
      (node (ref "R67") (pin "2") (pinfunction "2_2") (pintype "passive"))
      (node (ref "R68") (pin "1") (pinfunction "1_1") (pintype "passive"))
    )
    (net (code "57") (name "Net-(IN-P)") (class "Default")
      (node (ref "IN") (pin "1") (pinfunction "P_1") (pintype "passive"))
      (node (ref "R1") (pin "1") (pinfunction "1_1") (pintype "passive"))
      (node (ref "R29") (pin "1") (pinfunction "1_1") (pintype "passive"))
      (node (ref "R3") (pin "1") (pinfunction "1_1") (pintype "passive"))
      (node (ref "R4") (pin "1") (pinfunction "1_1") (pintype "passive"))
    )
    (net (code "58") (name "Net-(OUT-P)") (class "Default")
      (node (ref "OUT") (pin "1") (pinfunction "P_1") (pintype "passive"))
      (node (ref "R69") (pin "1") (pinfunction "1_1") (pintype "passive"))
    )
    (net (code "59") (name "Net-(Q2-P)") (class "Default")
      (node (ref "Q2") (pin "1") (pinfunction "P_1") (pintype "passive"))
      (node (ref "R66") (pin "1") (pinfunction "1_1") (pintype "passive"))
    )
    (net (code "60") (name "Net-(QA2-P)") (class "Default")
      (node (ref "QA2") (pin "1") (pinfunction "P_1") (pintype "passive"))
      (node (ref "R67") (pin "1") (pinfunction "1_1") (pintype "passive"))
    )
    (net (code "61") (name "Net-(U$1C-IN_N)") (class "Default")
      (node (ref "R57") (pin "2") (pinfunction "2_2") (pintype "passive"))
      (node (ref "R58") (pin "2") (pinfunction "2_2") (pintype "passive"))
      (node (ref "U$1") (pin "4") (pinfunction "IN_N_4") (pintype "input"))
    )
    (net (code "62") (name "Net-(U$1C-I_BIAS)") (class "Default")
      (node (ref "R63") (pin "1") (pinfunction "1_1") (pintype "passive"))
      (node (ref "R65") (pin "1") (pinfunction "1_1") (pintype "passive"))
      (node (ref "U$1") (pin "1") (pinfunction "I_BIAS_1") (pintype "input"))
    )
    (net (code "63") (name "Net-(U$1D-IN_N)") (class "Default")
      (node (ref "R53") (pin "2") (pinfunction "2_2") (pintype "passive"))
      (node (ref "R54") (pin "2") (pinfunction "2_2") (pintype "passive"))
      (node (ref "U$1") (pin "13") (pinfunction "IN_N_13") (pintype "input"))
    )
    (net (code "64") (name "Net-(U$1D-I_BIAS)") (class "Default")
      (node (ref "R62") (pin "1") (pinfunction "1_1") (pintype "passive"))
      (node (ref "R64") (pin "1") (pinfunction "1_1") (pintype "passive"))
      (node (ref "U$1") (pin "16") (pinfunction "I_BIAS_16") (pintype "input"))
    )
    (net (code "65") (name "unconnected-(IC1C-I_DIODE-Pad2)") (class "Default")
      (node (ref "IC1") (pin "2") (pinfunction "I_DIODE_2") (pintype "input"))
    )
    (net (code "66") (name "unconnected-(IC1D-I_DIODE-Pad15)") (class "Default")
      (node (ref "IC1") (pin "15") (pinfunction "I_DIODE_15") (pintype "input"))
    )
    (net (code "67") (name "unconnected-(IC11C-I_DIODE-Pad2)") (class "Default")
      (node (ref "IC11") (pin "2") (pinfunction "I_DIODE_2") (pintype "input"))
    )
    (net (code "68") (name "unconnected-(IC11D-I_DIODE-Pad15)") (class "Default")
      (node (ref "IC11") (pin "15") (pinfunction "I_DIODE_15") (pintype "input"))
    )
    (net (code "69") (name "unconnected-(IC14C-I_DIODE-Pad2)") (class "Default")
      (node (ref "IC14") (pin "2") (pinfunction "I_DIODE_2") (pintype "input"))
    )
    (net (code "70") (name "unconnected-(IC14D-I_DIODE-Pad15)") (class "Default")
      (node (ref "IC14") (pin "15") (pinfunction "I_DIODE_15") (pintype "input"))
    )
    (net (code "71") (name "unconnected-(IC18-ON1-Pad1)") (class "Default")
      (node (ref "IC18") (pin "1") (pinfunction "ON1_1") (pintype "passive"))
    )
    (net (code "72") (name "unconnected-(IC18-ON2-Pad5)") (class "Default")
      (node (ref "IC18") (pin "5") (pinfunction "ON2_5") (pintype "passive"))
    )
    (net (code "73") (name "unconnected-(IC18-OPT-Pad8)") (class "Default")
      (node (ref "IC18") (pin "8") (pinfunction "OPT_8") (pintype "passive"))
    )
    (net (code "74") (name "unconnected-(U$1C-I_DIODE-Pad2)") (class "Default")
      (node (ref "U$1") (pin "2") (pinfunction "I_DIODE_2") (pintype "input"))
    )
    (net (code "75") (name "unconnected-(U$1D-I_DIODE-Pad15)") (class "Default")
      (node (ref "U$1") (pin "15") (pinfunction "I_DIODE_15") (pintype "input"))
    )
  )
)
